# magic-donut.net
KiCad netlist of a schematic drawn in EAGLE
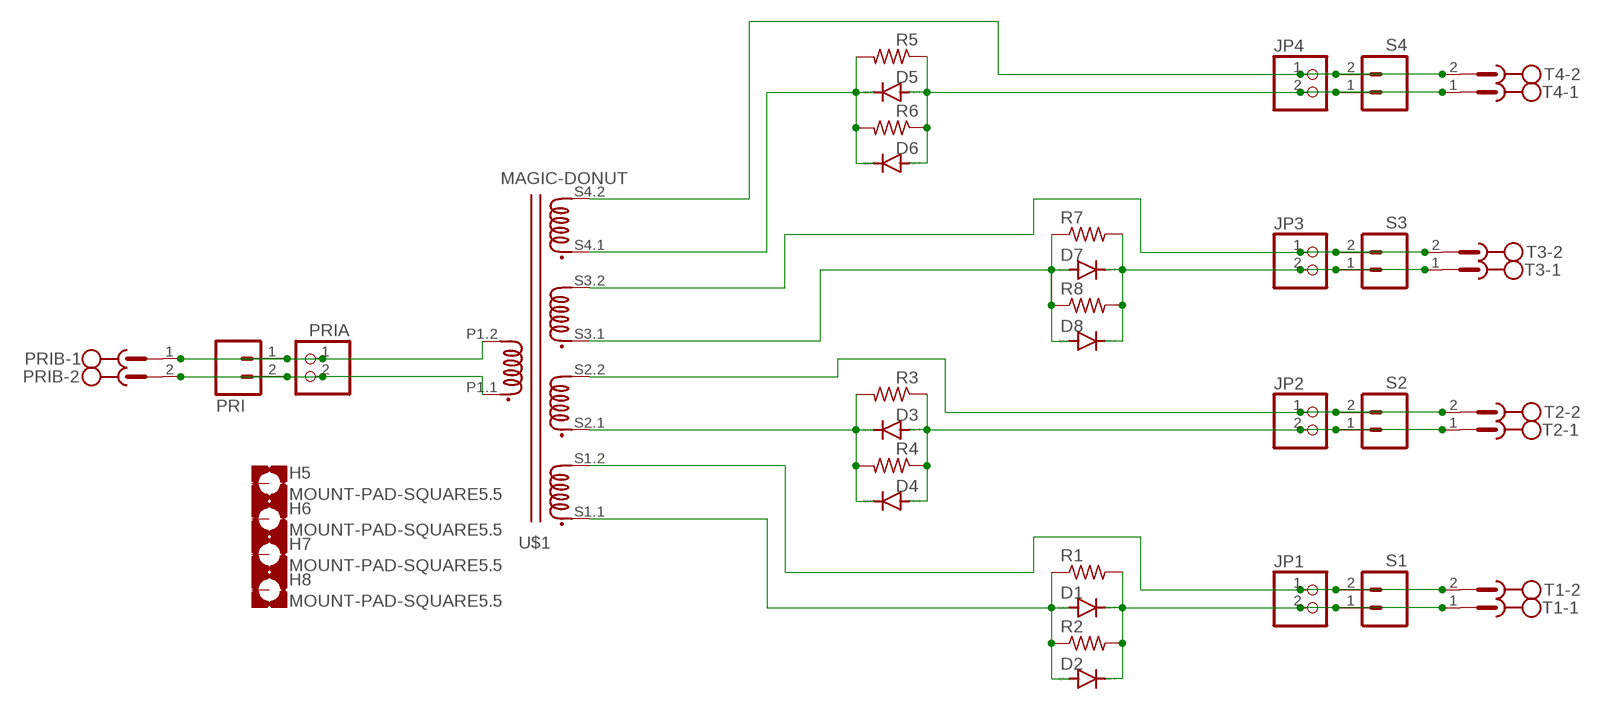
[diagram p0: schematic, sheet 1]

(export (version "E")
  (design (tool "Eeschema 10.0.6"))
  (components
    (comp (ref "D1")
      (value "DIODE-DO214AA")
      (footprint "eagle-import:DO214AA")
      (libsource (lib "eagle-import") (part "DIODE-DO214AA"))
    )
    (comp (ref "D2")
      (value "DIODE-DO201-15")
      (footprint "eagle-import:DO201-15")
      (libsource (lib "eagle-import") (part "DIODE-DO201-15"))
    )
    (comp (ref "D3")
      (value "DIODE-DO214AA")
      (footprint "eagle-import:DO214AA")
      (libsource (lib "eagle-import") (part "DIODE-DO214AA"))
    )
    (comp (ref "D4")
      (value "DIODE-DO201-15")
      (footprint "eagle-import:DO201-15")
      (libsource (lib "eagle-import") (part "DIODE-DO201-15"))
    )
    (comp (ref "D5")
      (value "DIODE-DO214AA")
      (footprint "eagle-import:DO214AA")
      (libsource (lib "eagle-import") (part "DIODE-DO214AA"))
    )
    (comp (ref "D6")
      (value "DIODE-DO201-15")
      (footprint "eagle-import:DO201-15")
      (libsource (lib "eagle-import") (part "DIODE-DO201-15"))
    )
    (comp (ref "D7")
      (value "DIODE-DO214AA")
      (footprint "eagle-import:DO214AA")
      (libsource (lib "eagle-import") (part "DIODE-DO214AA"))
    )
    (comp (ref "D8")
      (value "DIODE-DO201-15")
      (footprint "eagle-import:DO201-15")
      (libsource (lib "eagle-import") (part "DIODE-DO201-15"))
    )
    (comp (ref "H5")
      (value "MOUNT-PAD-SQUARE5.5")
      (footprint "eagle-import:5,5-PAD-SQUARE")
      (libsource (lib "eagle-import") (part "MOUNT-PAD-SQUARE5.5"))
    )
    (comp (ref "H6")
      (value "MOUNT-PAD-SQUARE5.5")
      (footprint "eagle-import:5,5-PAD-SQUARE")
      (libsource (lib "eagle-import") (part "MOUNT-PAD-SQUARE5.5"))
    )
    (comp (ref "H7")
      (value "MOUNT-PAD-SQUARE5.5")
      (footprint "eagle-import:5,5-PAD-SQUARE")
      (libsource (lib "eagle-import") (part "MOUNT-PAD-SQUARE5.5"))
    )
    (comp (ref "H8")
      (value "MOUNT-PAD-SQUARE5.5")
      (footprint "eagle-import:5,5-PAD-SQUARE")
      (libsource (lib "eagle-import") (part "MOUNT-PAD-SQUARE5.5"))
    )
    (comp (ref "JP1")
      (value "PINHD-1X2")
      (footprint "eagle-import:1X02")
      (libsource (lib "eagle-import") (part "PINHD-1X2"))
    )
    (comp (ref "JP2")
      (value "PINHD-1X2")
      (footprint "eagle-import:1X02")
      (libsource (lib "eagle-import") (part "PINHD-1X2"))
    )
    (comp (ref "JP3")
      (value "PINHD-1X2")
      (footprint "eagle-import:1X02")
      (libsource (lib "eagle-import") (part "PINHD-1X2"))
    )
    (comp (ref "JP4")
      (value "PINHD-1X2")
      (footprint "eagle-import:1X02")
      (libsource (lib "eagle-import") (part "PINHD-1X2"))
    )
    (comp (ref "PRI")
      (value "M02JST-PTH-2")
      (footprint "eagle-import:JST-2-PTH")
      (libsource (lib "eagle-import") (part "M02JST-PTH-2"))
    )
    (comp (ref "PRIA")
      (value "PINHD-1X2")
      (footprint "eagle-import:1X02")
      (libsource (lib "eagle-import") (part "PINHD-1X2"))
    )
    (comp (ref "PRIB")
      (value "MSTBV2")
      (footprint "eagle-import:MSTBV2")
      (libsource (lib "eagle-import") (part "MSTBV2"))
    )
    (comp (ref "R1")
      (value "R-US_R0805")
      (footprint "eagle-import:R0805")
      (libsource (lib "eagle-import") (part "R-US_R0805"))
    )
    (comp (ref "R2")
      (value "R-US_0207/7")
      (footprint "eagle-import:0207_7")
      (libsource (lib "eagle-import") (part "R-US_0207/7"))
    )
    (comp (ref "R3")
      (value "R-US_R0805")
      (footprint "eagle-import:R0805")
      (libsource (lib "eagle-import") (part "R-US_R0805"))
    )
    (comp (ref "R4")
      (value "R-US_0207/7")
      (footprint "eagle-import:0207_7")
      (libsource (lib "eagle-import") (part "R-US_0207/7"))
    )
    (comp (ref "R5")
      (value "R-US_R0805")
      (footprint "eagle-import:R0805")
      (libsource (lib "eagle-import") (part "R-US_R0805"))
    )
    (comp (ref "R6")
      (value "R-US_0207/7")
      (footprint "eagle-import:0207_7")
      (libsource (lib "eagle-import") (part "R-US_0207/7"))
    )
    (comp (ref "R7")
      (value "R-US_R0805")
      (footprint "eagle-import:R0805")
      (libsource (lib "eagle-import") (part "R-US_R0805"))
    )
    (comp (ref "R8")
      (value "R-US_0207/7")
      (footprint "eagle-import:0207_7")
      (libsource (lib "eagle-import") (part "R-US_0207/7"))
    )
    (comp (ref "S1")
      (value "M02JST-PTH-2")
      (footprint "eagle-import:JST-2-PTH")
      (libsource (lib "eagle-import") (part "M02JST-PTH-2"))
    )
    (comp (ref "S2")
      (value "M02JST-PTH-2")
      (footprint "eagle-import:JST-2-PTH")
      (libsource (lib "eagle-import") (part "M02JST-PTH-2"))
    )
    (comp (ref "S3")
      (value "M02JST-PTH-2")
      (footprint "eagle-import:JST-2-PTH")
      (libsource (lib "eagle-import") (part "M02JST-PTH-2"))
    )
    (comp (ref "S4")
      (value "M02JST-PTH-2")
      (footprint "eagle-import:JST-2-PTH")
      (libsource (lib "eagle-import") (part "M02JST-PTH-2"))
    )
    (comp (ref "T1")
      (value "MSTBV2")
      (footprint "eagle-import:MSTBV2")
      (libsource (lib "eagle-import") (part "MSTBV2"))
    )
    (comp (ref "T2")
      (value "MSTBV2")
      (footprint "eagle-import:MSTBV2")
      (libsource (lib "eagle-import") (part "MSTBV2"))
    )
    (comp (ref "T3")
      (value "MSTBV2")
      (footprint "eagle-import:MSTBV2")
      (libsource (lib "eagle-import") (part "MSTBV2"))
    )
    (comp (ref "T4")
      (value "MSTBV2")
      (footprint "eagle-import:MSTBV2")
      (libsource (lib "eagle-import") (part "MSTBV2"))
    )
    (comp (ref "U$1")
      (value "MAGIC-DONUT")
      (footprint "eagle-import:TOROID")
      (libsource (lib "eagle-import") (part "MAGIC-DONUT"))
    )
  )
  (nets
    (net (code "1") (name "Net-(D1-PadA)") (class "Default")
      (node (ref "D1") (pin "A") (pinfunction "A_A") (pintype "passive"))
      (node (ref "D2") (pin "A") (pinfunction "A_A") (pintype "passive"))
      (node (ref "R1") (pin "1") (pinfunction "1_1") (pintype "passive"))
      (node (ref "R2") (pin "1") (pinfunction "1_1") (pintype "passive"))
      (node (ref "U$1") (pin "S1.1") (pinfunction "S1.1_S1.1") (pintype "passive"))
    )
    (net (code "2") (name "Net-(D3-PadC)") (class "Default")
      (node (ref "D3") (pin "C") (pinfunction "C_C") (pintype "passive"))
      (node (ref "D4") (pin "C") (pinfunction "C_C") (pintype "passive"))
      (node (ref "R3") (pin "2") (pinfunction "2_2") (pintype "passive"))
      (node (ref "R4") (pin "2") (pinfunction "2_2") (pintype "passive"))
      (node (ref "U$1") (pin "S2.1") (pinfunction "S2.1_S2.1") (pintype "passive"))
    )
    (net (code "3") (name "Net-(D5-PadC)") (class "Default")
      (node (ref "D5") (pin "C") (pinfunction "C_C") (pintype "passive"))
      (node (ref "D6") (pin "C") (pinfunction "C_C") (pintype "passive"))
      (node (ref "R5") (pin "2") (pinfunction "2_2") (pintype "passive"))
      (node (ref "R6") (pin "2") (pinfunction "2_2") (pintype "passive"))
      (node (ref "U$1") (pin "S4.1") (pinfunction "S4.1_S4.1") (pintype "passive"))
    )
    (net (code "4") (name "Net-(D7-PadA)") (class "Default")
      (node (ref "D7") (pin "A") (pinfunction "A_A") (pintype "passive"))
      (node (ref "D8") (pin "A") (pinfunction "A_A") (pintype "passive"))
      (node (ref "R7") (pin "1") (pinfunction "1_1") (pintype "passive"))
      (node (ref "R8") (pin "1") (pinfunction "1_1") (pintype "passive"))
      (node (ref "U$1") (pin "S3.1") (pinfunction "S3.1_S3.1") (pintype "passive"))
    )
    (net (code "5") (name "Net-(PRIBA-SK)") (class "Default")
      (node (ref "PRI") (pin "1") (pinfunction "1_1") (pintype "passive"))
      (node (ref "PRIA") (pin "1") (pinfunction "1_1") (pintype "passive"))
      (node (ref "PRIB") (pin "1") (pinfunction "SK_1") (pintype "passive"))
      (node (ref "U$1") (pin "P1.2") (pinfunction "P1.2_P1.2") (pintype "passive"))
    )
    (net (code "6") (name "Net-(PRIBB-SK)") (class "Default")
      (node (ref "PRI") (pin "2") (pinfunction "2_2") (pintype "passive"))
      (node (ref "PRIA") (pin "2") (pinfunction "2_2") (pintype "passive"))
      (node (ref "PRIB") (pin "2") (pinfunction "SK_2") (pintype "passive"))
      (node (ref "U$1") (pin "P1.1") (pinfunction "P1.1_P1.1") (pintype "passive"))
    )
    (net (code "7") (name "Net-(T1A-SK)") (class "Default")
      (node (ref "D1") (pin "C") (pinfunction "C_C") (pintype "passive"))
      (node (ref "D2") (pin "C") (pinfunction "C_C") (pintype "passive"))
      (node (ref "JP1") (pin "2") (pinfunction "2_2") (pintype "passive"))
      (node (ref "R1") (pin "2") (pinfunction "2_2") (pintype "passive"))
      (node (ref "R2") (pin "2") (pinfunction "2_2") (pintype "passive"))
      (node (ref "S1") (pin "1") (pinfunction "1_1") (pintype "passive"))
      (node (ref "T1") (pin "1") (pinfunction "SK_1") (pintype "passive"))
    )
    (net (code "8") (name "Net-(T1B-SK)") (class "Default")
      (node (ref "JP1") (pin "1") (pinfunction "1_1") (pintype "passive"))
      (node (ref "S1") (pin "2") (pinfunction "2_2") (pintype "passive"))
      (node (ref "T1") (pin "2") (pinfunction "SK_2") (pintype "passive"))
      (node (ref "U$1") (pin "S1.2") (pinfunction "S1.2_S1.2") (pintype "passive"))
    )
    (net (code "9") (name "Net-(T2A-SK)") (class "Default")
      (node (ref "D3") (pin "A") (pinfunction "A_A") (pintype "passive"))
      (node (ref "D4") (pin "A") (pinfunction "A_A") (pintype "passive"))
      (node (ref "JP2") (pin "2") (pinfunction "2_2") (pintype "passive"))
      (node (ref "R3") (pin "1") (pinfunction "1_1") (pintype "passive"))
      (node (ref "R4") (pin "1") (pinfunction "1_1") (pintype "passive"))
      (node (ref "S2") (pin "1") (pinfunction "1_1") (pintype "passive"))
      (node (ref "T2") (pin "1") (pinfunction "SK_1") (pintype "passive"))
    )
    (net (code "10") (name "Net-(T2B-SK)") (class "Default")
      (node (ref "JP2") (pin "1") (pinfunction "1_1") (pintype "passive"))
      (node (ref "S2") (pin "2") (pinfunction "2_2") (pintype "passive"))
      (node (ref "T2") (pin "2") (pinfunction "SK_2") (pintype "passive"))
      (node (ref "U$1") (pin "S2.2") (pinfunction "S2.2_S2.2") (pintype "passive"))
    )
    (net (code "11") (name "Net-(T3A-SK)") (class "Default")
      (node (ref "D7") (pin "C") (pinfunction "C_C") (pintype "passive"))
      (node (ref "D8") (pin "C") (pinfunction "C_C") (pintype "passive"))
      (node (ref "JP3") (pin "2") (pinfunction "2_2") (pintype "passive"))
      (node (ref "R7") (pin "2") (pinfunction "2_2") (pintype "passive"))
      (node (ref "R8") (pin "2") (pinfunction "2_2") (pintype "passive"))
      (node (ref "S3") (pin "1") (pinfunction "1_1") (pintype "passive"))
      (node (ref "T3") (pin "1") (pinfunction "SK_1") (pintype "passive"))
    )
    (net (code "12") (name "Net-(T3B-SK)") (class "Default")
      (node (ref "JP3") (pin "1") (pinfunction "1_1") (pintype "passive"))
      (node (ref "S3") (pin "2") (pinfunction "2_2") (pintype "passive"))
      (node (ref "T3") (pin "2") (pinfunction "SK_2") (pintype "passive"))
      (node (ref "U$1") (pin "S3.2") (pinfunction "S3.2_S3.2") (pintype "passive"))
    )
    (net (code "13") (name "Net-(T4A-SK)") (class "Default")
      (node (ref "D5") (pin "A") (pinfunction "A_A") (pintype "passive"))
      (node (ref "D6") (pin "A") (pinfunction "A_A") (pintype "passive"))
      (node (ref "JP4") (pin "2") (pinfunction "2_2") (pintype "passive"))
      (node (ref "R5") (pin "1") (pinfunction "1_1") (pintype "passive"))
      (node (ref "R6") (pin "1") (pinfunction "1_1") (pintype "passive"))
      (node (ref "S4") (pin "1") (pinfunction "1_1") (pintype "passive"))
      (node (ref "T4") (pin "1") (pinfunction "SK_1") (pintype "passive"))
    )
    (net (code "14") (name "Net-(T4B-SK)") (class "Default")
      (node (ref "JP4") (pin "1") (pinfunction "1_1") (pintype "passive"))
      (node (ref "S4") (pin "2") (pinfunction "2_2") (pintype "passive"))
      (node (ref "T4") (pin "2") (pinfunction "SK_2") (pintype "passive"))
      (node (ref "U$1") (pin "S4.2") (pinfunction "S4.2_S4.2") (pintype "passive"))
    )
    (net (code "15") (name "unconnected-(H5-MOUNT-PadB5,5)") (class "Default")
      (node (ref "H5") (pin "B5,5") (pinfunction "MOUNT_B5,5") (pintype "passive"))
    )
    (net (code "16") (name "unconnected-(H6-MOUNT-PadB5,5)") (class "Default")
      (node (ref "H6") (pin "B5,5") (pinfunction "MOUNT_B5,5") (pintype "passive"))
    )
    (net (code "17") (name "unconnected-(H7-MOUNT-PadB5,5)") (class "Default")
      (node (ref "H7") (pin "B5,5") (pinfunction "MOUNT_B5,5") (pintype "passive"))
    )
    (net (code "18") (name "unconnected-(H8-MOUNT-PadB5,5)") (class "Default")
      (node (ref "H8") (pin "B5,5") (pinfunction "MOUNT_B5,5") (pintype "passive"))
    )
  )
)
